# Peripherals.net
KiCad netlist of a schematic drawn in Altium Designer
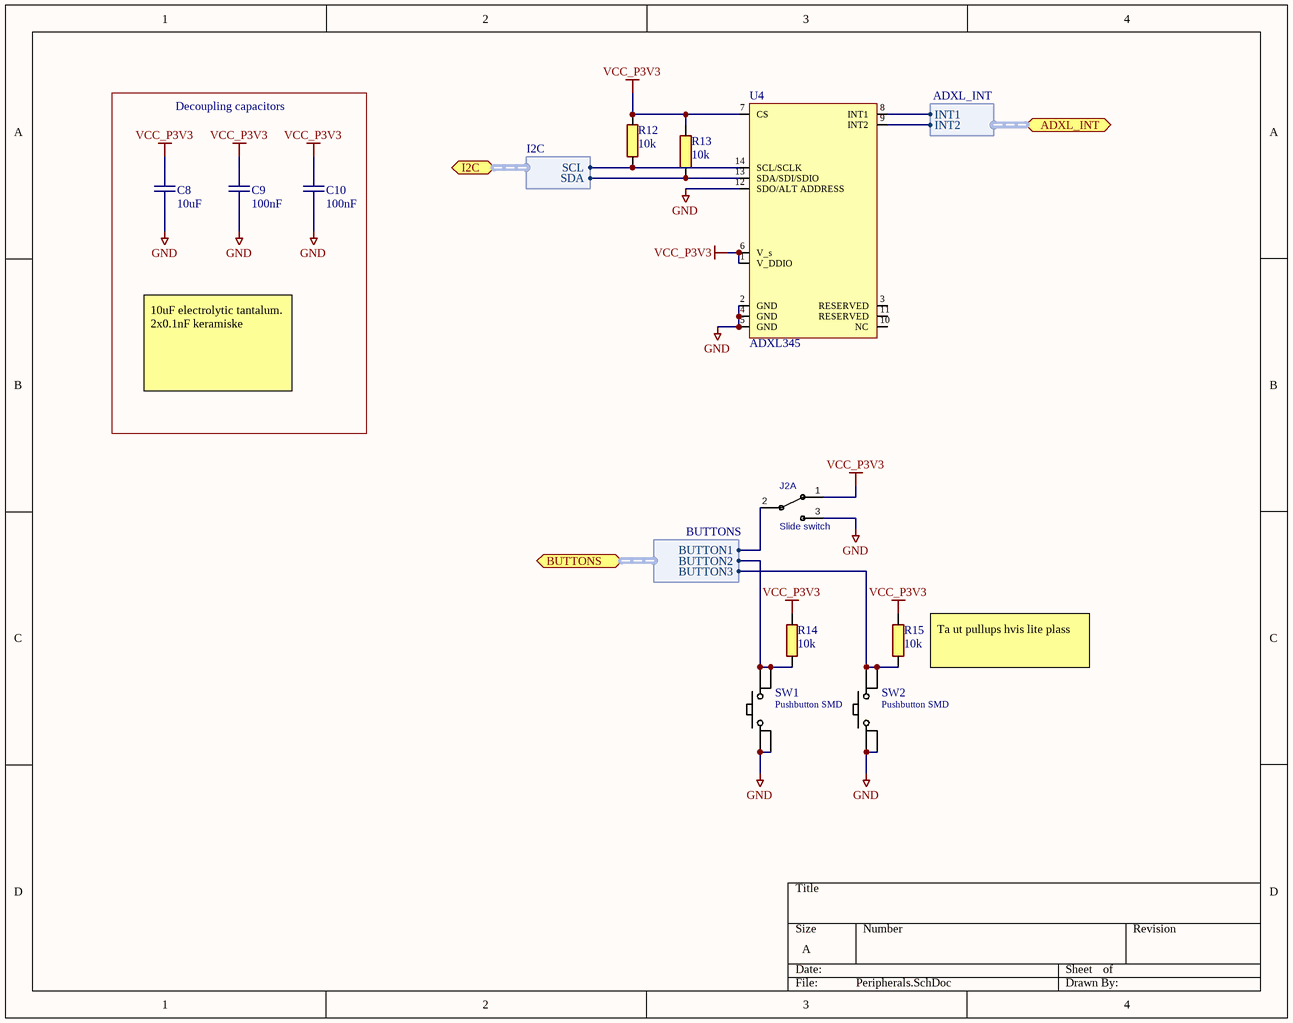
[diagram p0: Peripherals.SchDoc]

(export (version "E")
  (design (tool "Eeschema 10.0.6"))
  (components
    (comp (ref "C8")
      (value "10uF")
      (footprint "CAPC1206(3216)170_N")
      (description "X5R 50V 10%")
      (libsource (lib "OVLib") (part "CAP"))
    )
    (comp (ref "C9")
      (value "100nF")
      (footprint "CAPC0603(1608)55_N")
      (description "X7R 50V 5%")
      (libsource (lib "OVLib") (part "CAP"))
    )
    (comp (ref "C10")
      (value "100nF")
      (footprint "CAPC0603(1608)55_N")
      (description "X7R 50V 5%")
      (libsource (lib "OVLib") (part "CAP"))
    )
    (comp (ref "J2")
      (value "Slide switch")
      (footprint "OS202011MA0QS1")
      (description "Vinklet")
      (libsource (lib "OVLib") (part "Slide_switch_DPDT_RA"))
    )
    (comp (ref "R12")
      (value "10k")
      (footprint "RESC0603(1608)_N")
      (description "0.1W 1% Thick film resistor")
      (libsource (lib "OVLib") (part "Resistor2"))
    )
    (comp (ref "R13")
      (value "10k")
      (footprint "RESC0603(1608)_N")
      (description "0.1W 1% Thick film resistor")
      (libsource (lib "OVLib") (part "Resistor2"))
    )
    (comp (ref "R14")
      (value "10k")
      (footprint "RESC0603(1608)_N")
      (description "0.1W 1% Thick film resistor")
      (libsource (lib "OVLib") (part "Resistor2"))
    )
    (comp (ref "R15")
      (value "10k")
      (footprint "RESC0603(1608)_N")
      (description "0.1W 1% Thick film resistor")
      (libsource (lib "OVLib") (part "Resistor2"))
    )
    (comp (ref "SW1")
      (value "Pushbutton SMD")
      (footprint "SOIC254P500X160-4")
      (libsource (lib "OVLib") (part "Pushbutton"))
    )
    (comp (ref "SW2")
      (value "Pushbutton SMD")
      (footprint "SOIC254P500X160-4")
      (libsource (lib "OVLib") (part "Pushbutton"))
    )
    (comp (ref "U4") (value "ADXL345") (libsource (lib "Schlib1") (part "ADXL345")))
  )
  (nets
    (net (code "4") (name "/BUTTON1") (class "Default")
      (node (ref "J2") (pin "2") (pinfunction "2_2") (pintype "passive"))
    )
    (net (code "5") (name "/BUTTON2") (class "Default")
      (node (ref "R14") (pin "1") (pinfunction "1_1") (pintype "passive"))
      (node (ref "SW1") (pin "3") (pinfunction "3_3") (pintype "passive"))
      (node (ref "SW1") (pin "4") (pinfunction "4_4") (pintype "passive"))
    )
    (net (code "6") (name "/BUTTON3") (class "Default")
      (node (ref "R15") (pin "1") (pinfunction "1_1") (pintype "passive"))
      (node (ref "SW2") (pin "3") (pinfunction "3_3") (pintype "passive"))
      (node (ref "SW2") (pin "4") (pinfunction "4_4") (pintype "passive"))
    )
    (net (code "7") (name "/INT1") (class "Default")
      (node (ref "U4") (pin "8") (pinfunction "INT1_8") (pintype "passive"))
    )
    (net (code "8") (name "/INT2") (class "Default")
      (node (ref "U4") (pin "9") (pinfunction "INT2_9") (pintype "passive"))
    )
    (net (code "9") (name "/SCL") (class "Default")
      (node (ref "R12") (pin "1") (pinfunction "1_1") (pintype "passive"))
      (node (ref "U4") (pin "14") (pinfunction "SCL/SCLK_14") (pintype "passive"))
    )
    (net (code "10") (name "/SDA") (class "Default")
      (node (ref "R13") (pin "1") (pinfunction "1_1") (pintype "passive"))
      (node (ref "U4") (pin "13") (pinfunction "SDA/SDI/SDIO_13") (pintype "passive"))
    )
    (net (code "14") (name "GND") (class "Default")
      (node (ref "C10") (pin "1") (pinfunction "1_1") (pintype "passive"))
      (node (ref "C8") (pin "1") (pinfunction "1_1") (pintype "passive"))
      (node (ref "C9") (pin "1") (pinfunction "1_1") (pintype "passive"))
      (node (ref "J2") (pin "3") (pinfunction "3_3") (pintype "passive"))
      (node (ref "SW1") (pin "1") (pinfunction "1_1") (pintype "passive"))
      (node (ref "SW1") (pin "2") (pinfunction "2_2") (pintype "passive"))
      (node (ref "SW2") (pin "1") (pinfunction "1_1") (pintype "passive"))
      (node (ref "SW2") (pin "2") (pinfunction "2_2") (pintype "passive"))
      (node (ref "U4") (pin "12") (pinfunction "SDO/ALT_ADDRESS_12") (pintype "passive"))
      (node (ref "U4") (pin "2") (pinfunction "GND_2") (pintype "passive"))
      (node (ref "U4") (pin "4") (pinfunction "GND_4") (pintype "passive"))
      (node (ref "U4") (pin "5") (pinfunction "GND_5") (pintype "passive"))
    )
    (net (code "15") (name "VCC_P3V3") (class "Default")
      (node (ref "C10") (pin "2") (pinfunction "2_2") (pintype "passive"))
      (node (ref "C8") (pin "2") (pinfunction "2_2") (pintype "passive"))
      (node (ref "C9") (pin "2") (pinfunction "2_2") (pintype "passive"))
      (node (ref "J2") (pin "1") (pinfunction "1_1") (pintype "passive"))
      (node (ref "R12") (pin "2") (pinfunction "2_2") (pintype "passive"))
      (node (ref "R13") (pin "2") (pinfunction "2_2") (pintype "passive"))
      (node (ref "R14") (pin "2") (pinfunction "2_2") (pintype "passive"))
      (node (ref "R15") (pin "2") (pinfunction "2_2") (pintype "passive"))
      (node (ref "U4") (pin "1") (pinfunction "V_DDIO_1") (pintype "passive"))
      (node (ref "U4") (pin "6") (pinfunction "V_s_6") (pintype "passive"))
      (node (ref "U4") (pin "7") (pinfunction "CS_7") (pintype "passive"))
    )
    (net (code "16") (name "unconnected-(U4-NC-Pad10)") (class "Default")
      (node (ref "U4") (pin "10") (pinfunction "NC_10") (pintype "passive"))
    )
    (net (code "17") (name "unconnected-(U4-RESERVED-Pad3)") (class "Default")
      (node (ref "U4") (pin "3") (pinfunction "RESERVED_3") (pintype "passive"))
    )
    (net (code "18") (name "unconnected-(U4-RESERVED-Pad11)") (class "Default")
      (node (ref "U4") (pin "11") (pinfunction "RESERVED_11") (pintype "passive"))
    )
  )
)
